# MEM.net
KiCad netlist of a schematic drawn in Altium Designer
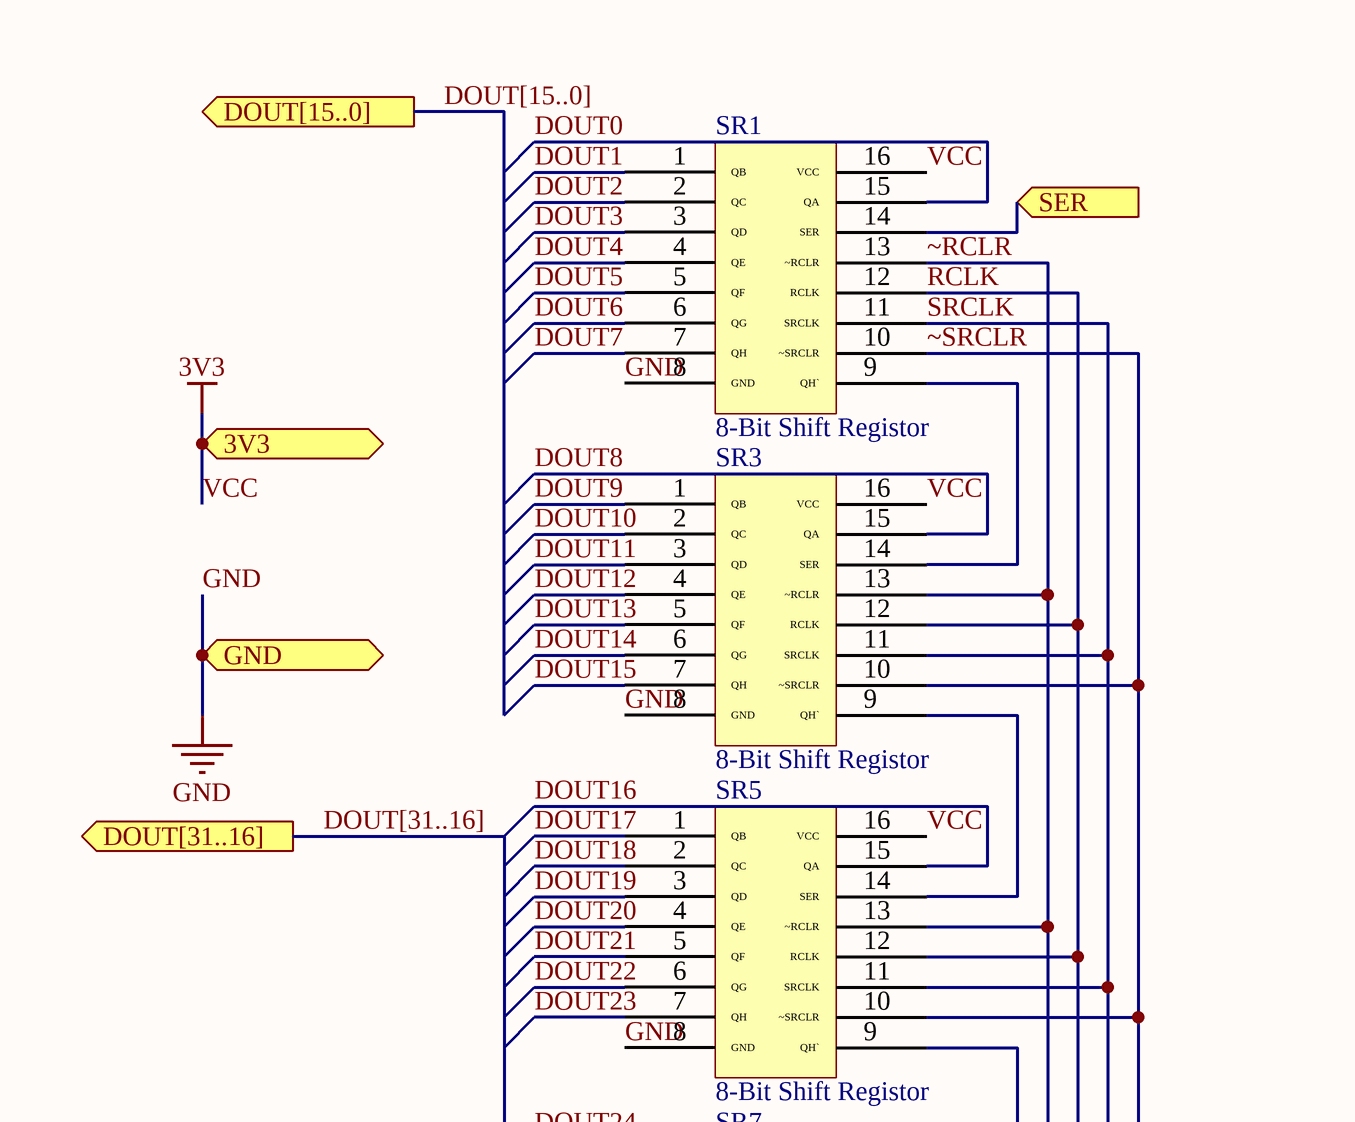
[diagram p0: MEM.SchDoc, top left]
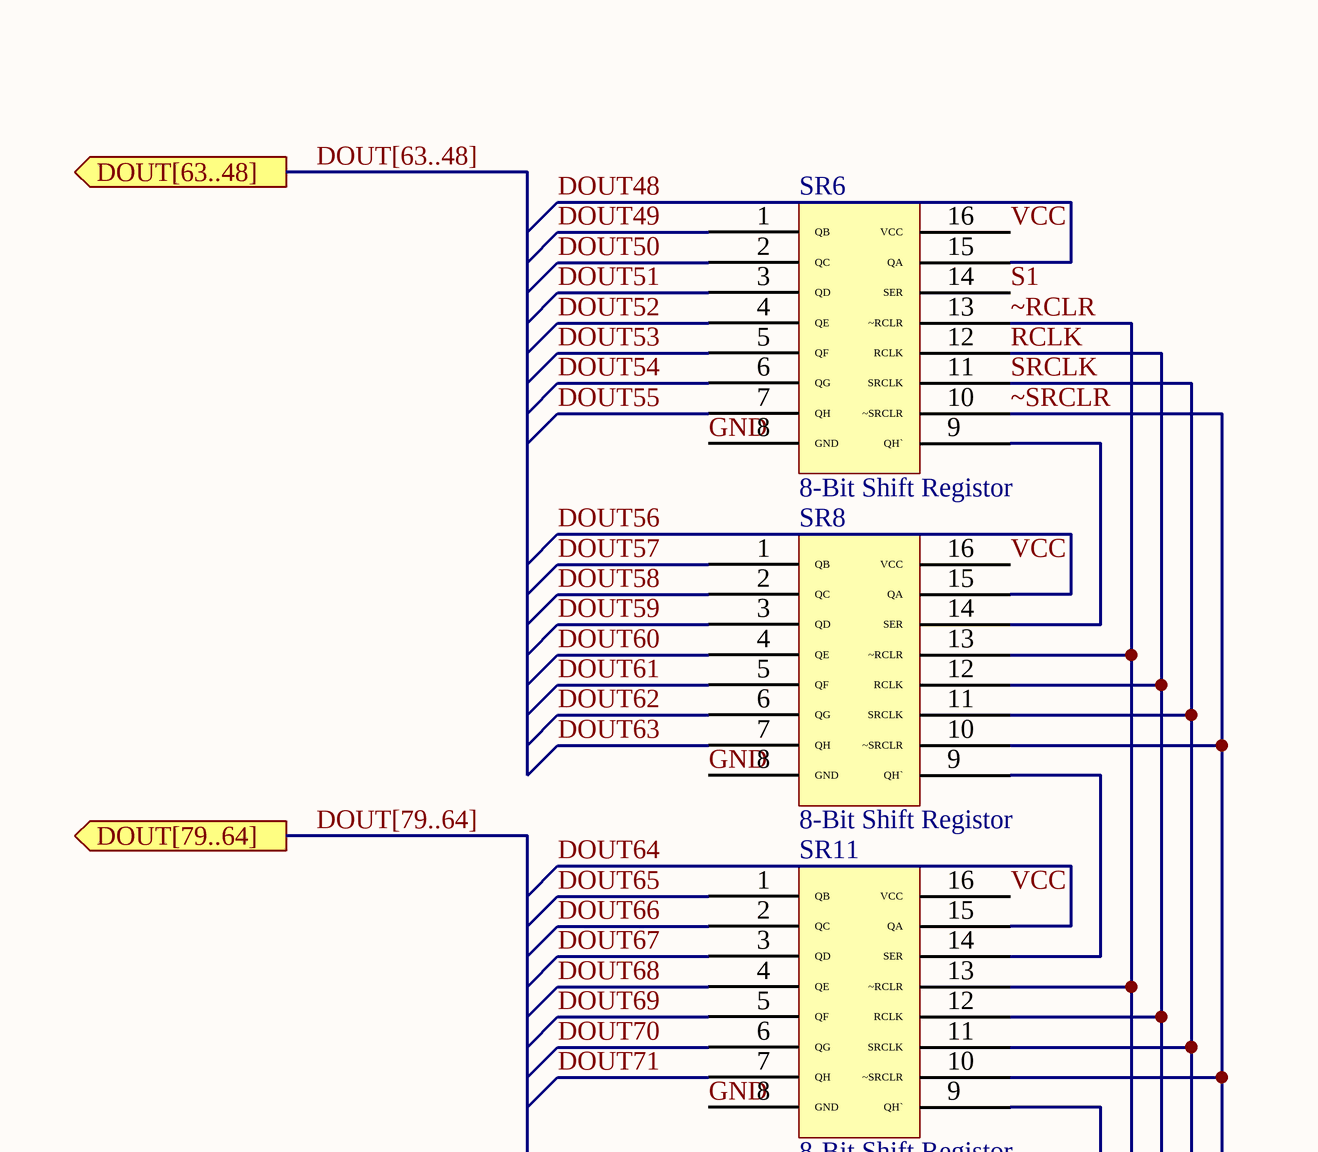
[diagram p1: MEM.SchDoc, top middle]
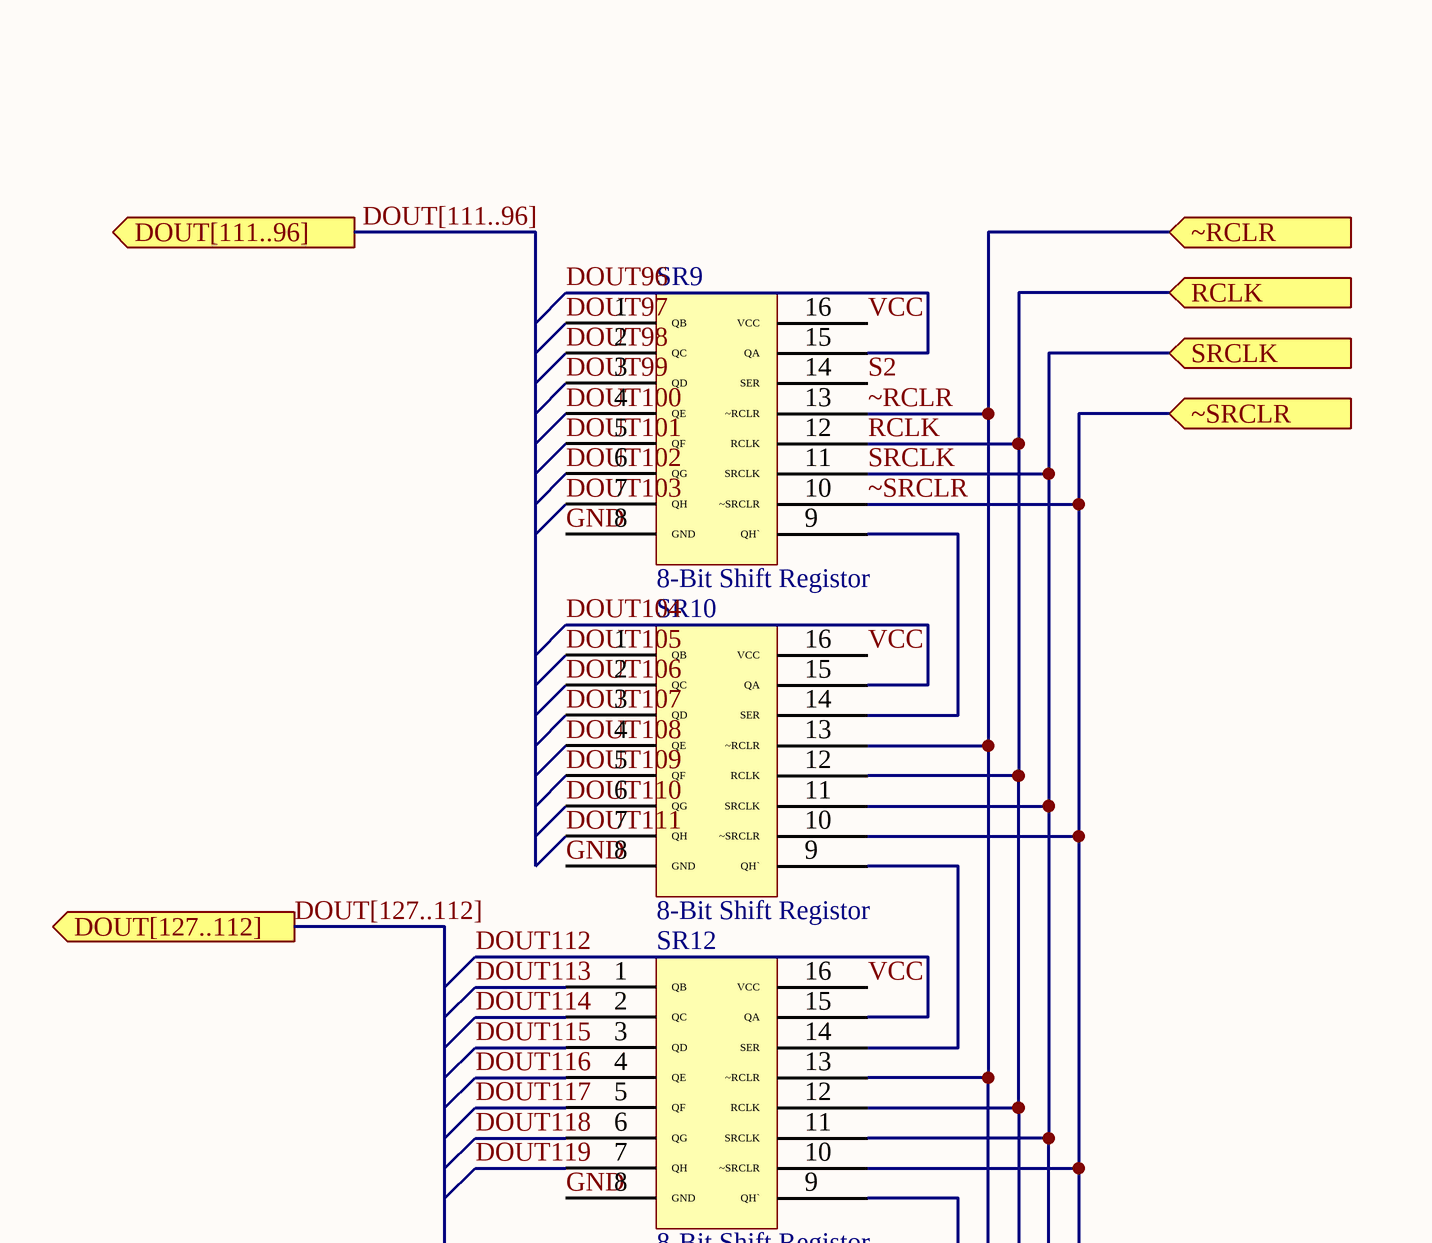
[diagram p2: MEM.SchDoc, top right]
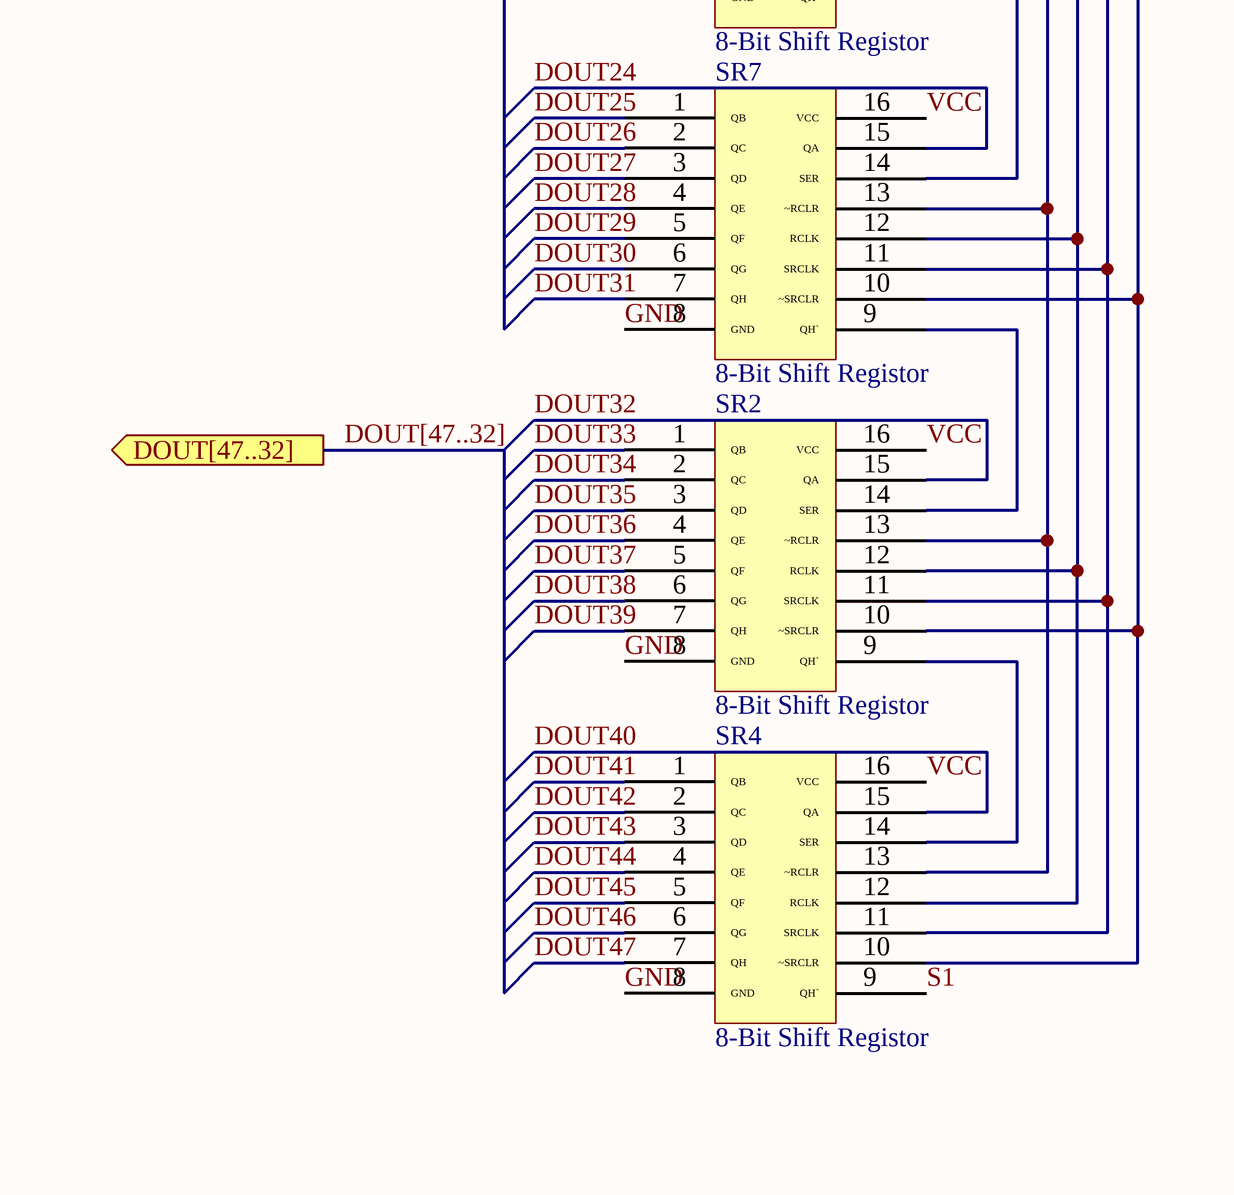
[diagram p3: MEM.SchDoc, bottom left]
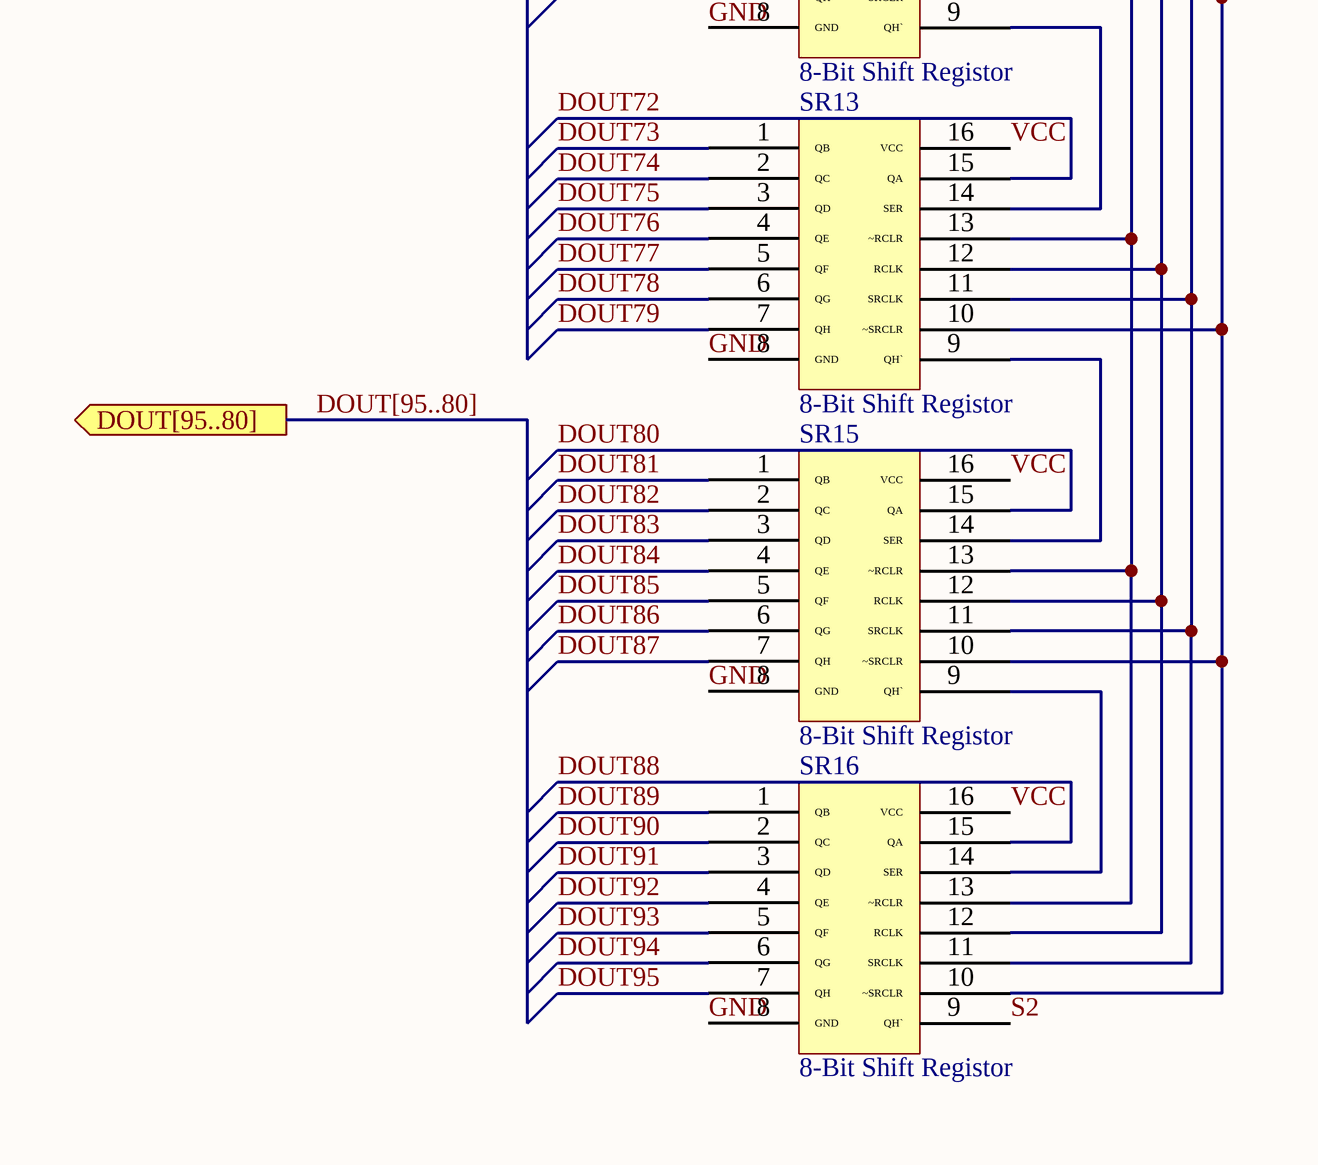
[diagram p4: MEM.SchDoc, bottom middle]
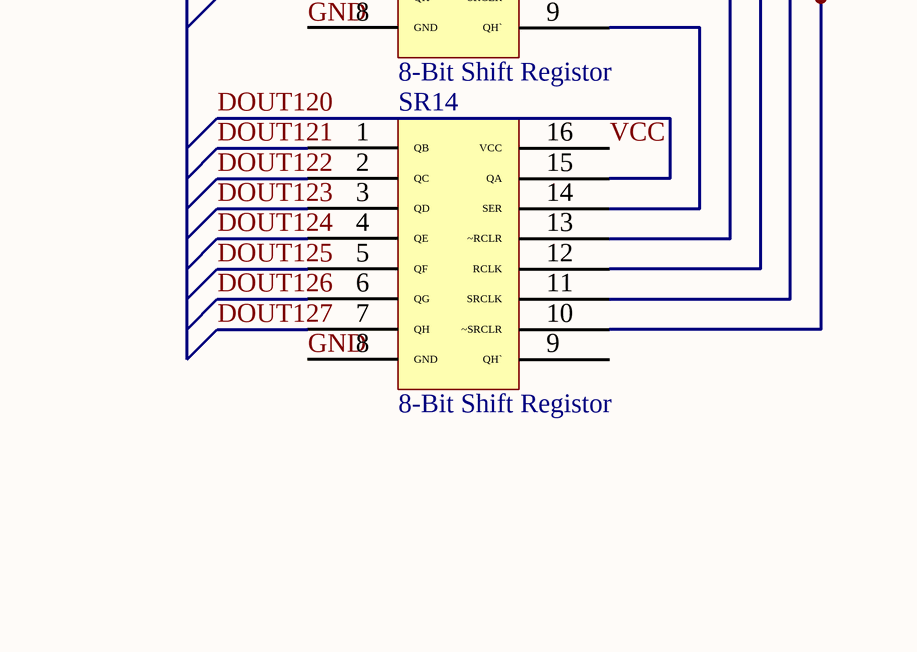
[diagram p5: MEM.SchDoc, bottom right]

(export (version "E")
  (design (tool "Eeschema 10.0.6"))
  (components
    (comp (ref "SR1")
      (value "8-Bit Shift Registor")
      (libsource (lib "NORMS_LIB") (part "8-Bit Shift Registor"))
    )
    (comp (ref "SR2")
      (value "8-Bit Shift Registor")
      (libsource (lib "NORMS_LIB") (part "8-Bit Shift Registor"))
    )
    (comp (ref "SR3")
      (value "8-Bit Shift Registor")
      (libsource (lib "NORMS_LIB") (part "8-Bit Shift Registor"))
    )
    (comp (ref "SR4")
      (value "8-Bit Shift Registor")
      (libsource (lib "NORMS_LIB") (part "8-Bit Shift Registor"))
    )
    (comp (ref "SR5")
      (value "8-Bit Shift Registor")
      (libsource (lib "NORMS_LIB") (part "8-Bit Shift Registor"))
    )
    (comp (ref "SR6")
      (value "8-Bit Shift Registor")
      (libsource (lib "NORMS_LIB") (part "8-Bit Shift Registor"))
    )
    (comp (ref "SR7")
      (value "8-Bit Shift Registor")
      (libsource (lib "NORMS_LIB") (part "8-Bit Shift Registor"))
    )
    (comp (ref "SR8")
      (value "8-Bit Shift Registor")
      (libsource (lib "NORMS_LIB") (part "8-Bit Shift Registor"))
    )
    (comp (ref "SR9")
      (value "8-Bit Shift Registor")
      (libsource (lib "NORMS_LIB") (part "8-Bit Shift Registor"))
    )
    (comp (ref "SR10")
      (value "8-Bit Shift Registor")
      (libsource (lib "NORMS_LIB") (part "8-Bit Shift Registor"))
    )
    (comp (ref "SR11")
      (value "8-Bit Shift Registor")
      (libsource (lib "NORMS_LIB") (part "8-Bit Shift Registor"))
    )
    (comp (ref "SR12")
      (value "8-Bit Shift Registor")
      (libsource (lib "NORMS_LIB") (part "8-Bit Shift Registor"))
    )
    (comp (ref "SR13")
      (value "8-Bit Shift Registor")
      (libsource (lib "NORMS_LIB") (part "8-Bit Shift Registor"))
    )
    (comp (ref "SR14")
      (value "8-Bit Shift Registor")
      (libsource (lib "NORMS_LIB") (part "8-Bit Shift Registor"))
    )
    (comp (ref "SR15")
      (value "8-Bit Shift Registor")
      (libsource (lib "NORMS_LIB") (part "8-Bit Shift Registor"))
    )
    (comp (ref "SR16")
      (value "8-Bit Shift Registor")
      (libsource (lib "NORMS_LIB") (part "8-Bit Shift Registor"))
    )
  )
  (nets
    (net (code "1") (name "/DOUT0") (class "Default")
      (node (ref "SR1") (pin "15") (pinfunction "QA_15") (pintype "passive"))
    )
    (net (code "2") (name "/DOUT1") (class "Default")
      (node (ref "SR1") (pin "1") (pinfunction "QB_1") (pintype "passive"))
    )
    (net (code "3") (name "/DOUT2") (class "Default")
      (node (ref "SR1") (pin "2") (pinfunction "QC_2") (pintype "passive"))
    )
    (net (code "4") (name "/DOUT3") (class "Default")
      (node (ref "SR1") (pin "3") (pinfunction "QD_3") (pintype "passive"))
    )
    (net (code "5") (name "/DOUT4") (class "Default")
      (node (ref "SR1") (pin "4") (pinfunction "QE_4") (pintype "passive"))
    )
    (net (code "6") (name "/DOUT5") (class "Default")
      (node (ref "SR1") (pin "5") (pinfunction "QF_5") (pintype "passive"))
    )
    (net (code "7") (name "/DOUT6") (class "Default")
      (node (ref "SR1") (pin "6") (pinfunction "QG_6") (pintype "passive"))
    )
    (net (code "8") (name "/DOUT7") (class "Default")
      (node (ref "SR1") (pin "7") (pinfunction "QH_7") (pintype "passive"))
    )
    (net (code "9") (name "/DOUT8") (class "Default")
      (node (ref "SR3") (pin "15") (pinfunction "QA_15") (pintype "passive"))
    )
    (net (code "10") (name "/DOUT9") (class "Default")
      (node (ref "SR3") (pin "1") (pinfunction "QB_1") (pintype "passive"))
    )
    (net (code "11") (name "/DOUT10") (class "Default")
      (node (ref "SR3") (pin "2") (pinfunction "QC_2") (pintype "passive"))
    )
    (net (code "12") (name "/DOUT11") (class "Default")
      (node (ref "SR3") (pin "3") (pinfunction "QD_3") (pintype "passive"))
    )
    (net (code "13") (name "/DOUT12") (class "Default")
      (node (ref "SR3") (pin "4") (pinfunction "QE_4") (pintype "passive"))
    )
    (net (code "14") (name "/DOUT13") (class "Default")
      (node (ref "SR3") (pin "5") (pinfunction "QF_5") (pintype "passive"))
    )
    (net (code "15") (name "/DOUT14") (class "Default")
      (node (ref "SR3") (pin "6") (pinfunction "QG_6") (pintype "passive"))
    )
    (net (code "16") (name "/DOUT15") (class "Default")
      (node (ref "SR3") (pin "7") (pinfunction "QH_7") (pintype "passive"))
    )
    (net (code "17") (name "/DOUT16") (class "Default")
      (node (ref "SR5") (pin "15") (pinfunction "QA_15") (pintype "passive"))
    )
    (net (code "18") (name "/DOUT17") (class "Default")
      (node (ref "SR5") (pin "1") (pinfunction "QB_1") (pintype "passive"))
    )
    (net (code "19") (name "/DOUT18") (class "Default")
      (node (ref "SR5") (pin "2") (pinfunction "QC_2") (pintype "passive"))
    )
    (net (code "20") (name "/DOUT19") (class "Default")
      (node (ref "SR5") (pin "3") (pinfunction "QD_3") (pintype "passive"))
    )
    (net (code "21") (name "/DOUT20") (class "Default")
      (node (ref "SR5") (pin "4") (pinfunction "QE_4") (pintype "passive"))
    )
    (net (code "22") (name "/DOUT21") (class "Default")
      (node (ref "SR5") (pin "5") (pinfunction "QF_5") (pintype "passive"))
    )
    (net (code "23") (name "/DOUT22") (class "Default")
      (node (ref "SR5") (pin "6") (pinfunction "QG_6") (pintype "passive"))
    )
    (net (code "24") (name "/DOUT23") (class "Default")
      (node (ref "SR5") (pin "7") (pinfunction "QH_7") (pintype "passive"))
    )
    (net (code "25") (name "/DOUT24") (class "Default")
      (node (ref "SR7") (pin "15") (pinfunction "QA_15") (pintype "passive"))
    )
    (net (code "26") (name "/DOUT25") (class "Default")
      (node (ref "SR7") (pin "1") (pinfunction "QB_1") (pintype "passive"))
    )
    (net (code "27") (name "/DOUT26") (class "Default")
      (node (ref "SR7") (pin "2") (pinfunction "QC_2") (pintype "passive"))
    )
    (net (code "28") (name "/DOUT27") (class "Default")
      (node (ref "SR7") (pin "3") (pinfunction "QD_3") (pintype "passive"))
    )
    (net (code "29") (name "/DOUT28") (class "Default")
      (node (ref "SR7") (pin "4") (pinfunction "QE_4") (pintype "passive"))
    )
    (net (code "30") (name "/DOUT29") (class "Default")
      (node (ref "SR7") (pin "5") (pinfunction "QF_5") (pintype "passive"))
    )
    (net (code "31") (name "/DOUT30") (class "Default")
      (node (ref "SR7") (pin "6") (pinfunction "QG_6") (pintype "passive"))
    )
    (net (code "32") (name "/DOUT31") (class "Default")
      (node (ref "SR7") (pin "7") (pinfunction "QH_7") (pintype "passive"))
    )
    (net (code "33") (name "/DOUT32") (class "Default")
      (node (ref "SR2") (pin "15") (pinfunction "QA_15") (pintype "passive"))
    )
    (net (code "34") (name "/DOUT33") (class "Default")
      (node (ref "SR2") (pin "1") (pinfunction "QB_1") (pintype "passive"))
    )
    (net (code "35") (name "/DOUT34") (class "Default")
      (node (ref "SR2") (pin "2") (pinfunction "QC_2") (pintype "passive"))
    )
    (net (code "36") (name "/DOUT35") (class "Default")
      (node (ref "SR2") (pin "3") (pinfunction "QD_3") (pintype "passive"))
    )
    (net (code "37") (name "/DOUT36") (class "Default")
      (node (ref "SR2") (pin "4") (pinfunction "QE_4") (pintype "passive"))
    )
    (net (code "38") (name "/DOUT37") (class "Default")
      (node (ref "SR2") (pin "5") (pinfunction "QF_5") (pintype "passive"))
    )
    (net (code "39") (name "/DOUT38") (class "Default")
      (node (ref "SR2") (pin "6") (pinfunction "QG_6") (pintype "passive"))
    )
    (net (code "40") (name "/DOUT39") (class "Default")
      (node (ref "SR2") (pin "7") (pinfunction "QH_7") (pintype "passive"))
    )
    (net (code "41") (name "/DOUT40") (class "Default")
      (node (ref "SR4") (pin "15") (pinfunction "QA_15") (pintype "passive"))
    )
    (net (code "42") (name "/DOUT41") (class "Default")
      (node (ref "SR4") (pin "1") (pinfunction "QB_1") (pintype "passive"))
    )
    (net (code "43") (name "/DOUT42") (class "Default")
      (node (ref "SR4") (pin "2") (pinfunction "QC_2") (pintype "passive"))
    )
    (net (code "44") (name "/DOUT43") (class "Default")
      (node (ref "SR4") (pin "3") (pinfunction "QD_3") (pintype "passive"))
    )
    (net (code "45") (name "/DOUT44") (class "Default")
      (node (ref "SR4") (pin "4") (pinfunction "QE_4") (pintype "passive"))
    )
    (net (code "46") (name "/DOUT45") (class "Default")
      (node (ref "SR4") (pin "5") (pinfunction "QF_5") (pintype "passive"))
    )
    (net (code "47") (name "/DOUT46") (class "Default")
      (node (ref "SR4") (pin "6") (pinfunction "QG_6") (pintype "passive"))
    )
    (net (code "48") (name "/DOUT47") (class "Default")
      (node (ref "SR4") (pin "7") (pinfunction "QH_7") (pintype "passive"))
    )
    (net (code "49") (name "/DOUT48") (class "Default")
      (node (ref "SR6") (pin "15") (pinfunction "QA_15") (pintype "passive"))
    )
    (net (code "50") (name "/DOUT49") (class "Default")
      (node (ref "SR6") (pin "1") (pinfunction "QB_1") (pintype "passive"))
    )
    (net (code "51") (name "/DOUT50") (class "Default")
      (node (ref "SR6") (pin "2") (pinfunction "QC_2") (pintype "passive"))
    )
    (net (code "52") (name "/DOUT51") (class "Default")
      (node (ref "SR6") (pin "3") (pinfunction "QD_3") (pintype "passive"))
    )
    (net (code "53") (name "/DOUT52") (class "Default")
      (node (ref "SR6") (pin "4") (pinfunction "QE_4") (pintype "passive"))
    )
    (net (code "54") (name "/DOUT53") (class "Default")
      (node (ref "SR6") (pin "5") (pinfunction "QF_5") (pintype "passive"))
    )
    (net (code "55") (name "/DOUT54") (class "Default")
      (node (ref "SR6") (pin "6") (pinfunction "QG_6") (pintype "passive"))
    )
    (net (code "56") (name "/DOUT55") (class "Default")
      (node (ref "SR6") (pin "7") (pinfunction "QH_7") (pintype "passive"))
    )
    (net (code "57") (name "/DOUT56") (class "Default")
      (node (ref "SR8") (pin "15") (pinfunction "QA_15") (pintype "passive"))
    )
    (net (code "58") (name "/DOUT57") (class "Default")
      (node (ref "SR8") (pin "1") (pinfunction "QB_1") (pintype "passive"))
    )
    (net (code "59") (name "/DOUT58") (class "Default")
      (node (ref "SR8") (pin "2") (pinfunction "QC_2") (pintype "passive"))
    )
    (net (code "60") (name "/DOUT59") (class "Default")
      (node (ref "SR8") (pin "3") (pinfunction "QD_3") (pintype "passive"))
    )
    (net (code "61") (name "/DOUT60") (class "Default")
      (node (ref "SR8") (pin "4") (pinfunction "QE_4") (pintype "passive"))
    )
    (net (code "62") (name "/DOUT61") (class "Default")
      (node (ref "SR8") (pin "5") (pinfunction "QF_5") (pintype "passive"))
    )
    (net (code "63") (name "/DOUT62") (class "Default")
      (node (ref "SR8") (pin "6") (pinfunction "QG_6") (pintype "passive"))
    )
    (net (code "64") (name "/DOUT63") (class "Default")
      (node (ref "SR8") (pin "7") (pinfunction "QH_7") (pintype "passive"))
    )
    (net (code "65") (name "/DOUT64") (class "Default")
      (node (ref "SR11") (pin "15") (pinfunction "QA_15") (pintype "passive"))
    )
    (net (code "66") (name "/DOUT65") (class "Default")
      (node (ref "SR11") (pin "1") (pinfunction "QB_1") (pintype "passive"))
    )
    (net (code "67") (name "/DOUT66") (class "Default")
      (node (ref "SR11") (pin "2") (pinfunction "QC_2") (pintype "passive"))
    )
    (net (code "68") (name "/DOUT67") (class "Default")
      (node (ref "SR11") (pin "3") (pinfunction "QD_3") (pintype "passive"))
    )
    (net (code "69") (name "/DOUT68") (class "Default")
      (node (ref "SR11") (pin "4") (pinfunction "QE_4") (pintype "passive"))
    )
    (net (code "70") (name "/DOUT69") (class "Default")
      (node (ref "SR11") (pin "5") (pinfunction "QF_5") (pintype "passive"))
    )
    (net (code "71") (name "/DOUT70") (class "Default")
      (node (ref "SR11") (pin "6") (pinfunction "QG_6") (pintype "passive"))
    )
    (net (code "72") (name "/DOUT71") (class "Default")
      (node (ref "SR11") (pin "7") (pinfunction "QH_7") (pintype "passive"))
    )
    (net (code "73") (name "/DOUT72") (class "Default")
      (node (ref "SR13") (pin "15") (pinfunction "QA_15") (pintype "passive"))
    )
    (net (code "74") (name "/DOUT73") (class "Default")
      (node (ref "SR13") (pin "1") (pinfunction "QB_1") (pintype "passive"))
    )
    (net (code "75") (name "/DOUT74") (class "Default")
      (node (ref "SR13") (pin "2") (pinfunction "QC_2") (pintype "passive"))
    )
    (net (code "76") (name "/DOUT75") (class "Default")
      (node (ref "SR13") (pin "3") (pinfunction "QD_3") (pintype "passive"))
    )
    (net (code "77") (name "/DOUT76") (class "Default")
      (node (ref "SR13") (pin "4") (pinfunction "QE_4") (pintype "passive"))
    )
    (net (code "78") (name "/DOUT77") (class "Default")
      (node (ref "SR13") (pin "5") (pinfunction "QF_5") (pintype "passive"))
    )
    (net (code "79") (name "/DOUT78") (class "Default")
      (node (ref "SR13") (pin "6") (pinfunction "QG_6") (pintype "passive"))
    )
    (net (code "80") (name "/DOUT79") (class "Default")
      (node (ref "SR13") (pin "7") (pinfunction "QH_7") (pintype "passive"))
    )
    (net (code "81") (name "/DOUT80") (class "Default")
      (node (ref "SR15") (pin "15") (pinfunction "QA_15") (pintype "passive"))
    )
    (net (code "82") (name "/DOUT81") (class "Default")
      (node (ref "SR15") (pin "1") (pinfunction "QB_1") (pintype "passive"))
    )
    (net (code "83") (name "/DOUT82") (class "Default")
      (node (ref "SR15") (pin "2") (pinfunction "QC_2") (pintype "passive"))
    )
    (net (code "84") (name "/DOUT83") (class "Default")
      (node (ref "SR15") (pin "3") (pinfunction "QD_3") (pintype "passive"))
    )
    (net (code "85") (name "/DOUT84") (class "Default")
      (node (ref "SR15") (pin "4") (pinfunction "QE_4") (pintype "passive"))
    )
    (net (code "86") (name "/DOUT85") (class "Default")
      (node (ref "SR15") (pin "5") (pinfunction "QF_5") (pintype "passive"))
    )
    (net (code "87") (name "/DOUT86") (class "Default")
      (node (ref "SR15") (pin "6") (pinfunction "QG_6") (pintype "passive"))
    )
    (net (code "88") (name "/DOUT87") (class "Default")
      (node (ref "SR15") (pin "7") (pinfunction "QH_7") (pintype "passive"))
    )
    (net (code "89") (name "/DOUT88") (class "Default")
      (node (ref "SR16") (pin "15") (pinfunction "QA_15") (pintype "passive"))
    )
    (net (code "90") (name "/DOUT89") (class "Default")
      (node (ref "SR16") (pin "1") (pinfunction "QB_1") (pintype "passive"))
    )
    (net (code "91") (name "/DOUT90") (class "Default")
      (node (ref "SR16") (pin "2") (pinfunction "QC_2") (pintype "passive"))
    )
    (net (code "92") (name "/DOUT91") (class "Default")
      (node (ref "SR16") (pin "3") (pinfunction "QD_3") (pintype "passive"))
    )
    (net (code "93") (name "/DOUT92") (class "Default")
      (node (ref "SR16") (pin "4") (pinfunction "QE_4") (pintype "passive"))
    )
    (net (code "94") (name "/DOUT93") (class "Default")
      (node (ref "SR16") (pin "5") (pinfunction "QF_5") (pintype "passive"))
    )
    (net (code "95") (name "/DOUT94") (class "Default")
      (node (ref "SR16") (pin "6") (pinfunction "QG_6") (pintype "passive"))
    )
    (net (code "96") (name "/DOUT95") (class "Default")
      (node (ref "SR16") (pin "7") (pinfunction "QH_7") (pintype "passive"))
    )
    (net (code "97") (name "/DOUT96") (class "Default")
      (node (ref "SR9") (pin "15") (pinfunction "QA_15") (pintype "passive"))
    )
    (net (code "98") (name "/DOUT97") (class "Default")
      (node (ref "SR9") (pin "1") (pinfunction "QB_1") (pintype "passive"))
    )
    (net (code "99") (name "/DOUT98") (class "Default")
      (node (ref "SR9") (pin "2") (pinfunction "QC_2") (pintype "passive"))
    )
    (net (code "100") (name "/DOUT99") (class "Default")
      (node (ref "SR9") (pin "3") (pinfunction "QD_3") (pintype "passive"))
    )
    (net (code "101") (name "/DOUT100") (class "Default")
      (node (ref "SR9") (pin "4") (pinfunction "QE_4") (pintype "passive"))
    )
    (net (code "102") (name "/DOUT101") (class "Default")
      (node (ref "SR9") (pin "5") (pinfunction "QF_5") (pintype "passive"))
    )
    (net (code "103") (name "/DOUT102") (class "Default")
      (node (ref "SR9") (pin "6") (pinfunction "QG_6") (pintype "passive"))
    )
    (net (code "104") (name "/DOUT103") (class "Default")
      (node (ref "SR9") (pin "7") (pinfunction "QH_7") (pintype "passive"))
    )
    (net (code "105") (name "/DOUT104") (class "Default")
      (node (ref "SR10") (pin "15") (pinfunction "QA_15") (pintype "passive"))
    )
    (net (code "106") (name "/DOUT105") (class "Default")
      (node (ref "SR10") (pin "1") (pinfunction "QB_1") (pintype "passive"))
    )
    (net (code "107") (name "/DOUT106") (class "Default")
      (node (ref "SR10") (pin "2") (pinfunction "QC_2") (pintype "passive"))
    )
    (net (code "108") (name "/DOUT107") (class "Default")
      (node (ref "SR10") (pin "3") (pinfunction "QD_3") (pintype "passive"))
    )
    (net (code "109") (name "/DOUT108") (class "Default")
      (node (ref "SR10") (pin "4") (pinfunction "QE_4") (pintype "passive"))
    )
    (net (code "110") (name "/DOUT109") (class "Default")
      (node (ref "SR10") (pin "5") (pinfunction "QF_5") (pintype "passive"))
    )
    (net (code "111") (name "/DOUT110") (class "Default")
      (node (ref "SR10") (pin "6") (pinfunction "QG_6") (pintype "passive"))
    )
    (net (code "112") (name "/DOUT111") (class "Default")
      (node (ref "SR10") (pin "7") (pinfunction "QH_7") (pintype "passive"))
    )
    (net (code "113") (name "/DOUT112") (class "Default")
      (node (ref "SR12") (pin "15") (pinfunction "QA_15") (pintype "passive"))
    )
    (net (code "114") (name "/DOUT113") (class "Default")
      (node (ref "SR12") (pin "1") (pinfunction "QB_1") (pintype "passive"))
    )
    (net (code "115") (name "/DOUT114") (class "Default")
      (node (ref "SR12") (pin "2") (pinfunction "QC_2") (pintype "passive"))
    )
    (net (code "116") (name "/DOUT115") (class "Default")
      (node (ref "SR12") (pin "3") (pinfunction "QD_3") (pintype "passive"))
    )
    (net (code "117") (name "/DOUT116") (class "Default")
      (node (ref "SR12") (pin "4") (pinfunction "QE_4") (pintype "passive"))
    )
    (net (code "118") (name "/DOUT117") (class "Default")
      (node (ref "SR12") (pin "5") (pinfunction "QF_5") (pintype "passive"))
    )
    (net (code "119") (name "/DOUT118") (class "Default")
      (node (ref "SR12") (pin "6") (pinfunction "QG_6") (pintype "passive"))
    )
    (net (code "120") (name "/DOUT119") (class "Default")
      (node (ref "SR12") (pin "7") (pinfunction "QH_7") (pintype "passive"))
    )
    (net (code "121") (name "/DOUT120") (class "Default")
      (node (ref "SR14") (pin "15") (pinfunction "QA_15") (pintype "passive"))
    )
    (net (code "122") (name "/DOUT121") (class "Default")
      (node (ref "SR14") (pin "1") (pinfunction "QB_1") (pintype "passive"))
    )
    (net (code "123") (name "/DOUT122") (class "Default")
      (node (ref "SR14") (pin "2") (pinfunction "QC_2") (pintype "passive"))
    )
    (net (code "124") (name "/DOUT123") (class "Default")
      (node (ref "SR14") (pin "3") (pinfunction "QD_3") (pintype "passive"))
    )
    (net (code "125") (name "/DOUT124") (class "Default")
      (node (ref "SR14") (pin "4") (pinfunction "QE_4") (pintype "passive"))
    )
    (net (code "126") (name "/DOUT125") (class "Default")
      (node (ref "SR14") (pin "5") (pinfunction "QF_5") (pintype "passive"))
    )
    (net (code "127") (name "/DOUT126") (class "Default")
      (node (ref "SR14") (pin "6") (pinfunction "QG_6") (pintype "passive"))
    )
    (net (code "128") (name "/DOUT127") (class "Default")
      (node (ref "SR14") (pin "7") (pinfunction "QH_7") (pintype "passive"))
    )
    (net (code "137") (name "/RCLK") (class "Default")
      (node (ref "SR1") (pin "12") (pinfunction "RCLK_12") (pintype "passive"))
      (node (ref "SR10") (pin "12") (pinfunction "RCLK_12") (pintype "passive"))
      (node (ref "SR11") (pin "12") (pinfunction "RCLK_12") (pintype "passive"))
      (node (ref "SR12") (pin "12") (pinfunction "RCLK_12") (pintype "passive"))
      (node (ref "SR13") (pin "12") (pinfunction "RCLK_12") (pintype "passive"))
      (node (ref "SR14") (pin "12") (pinfunction "RCLK_12") (pintype "passive"))
      (node (ref "SR15") (pin "12") (pinfunction "RCLK_12") (pintype "passive"))
      (node (ref "SR16") (pin "12") (pinfunction "RCLK_12") (pintype "passive"))
      (node (ref "SR2") (pin "12") (pinfunction "RCLK_12") (pintype "passive"))
      (node (ref "SR3") (pin "12") (pinfunction "RCLK_12") (pintype "passive"))
      (node (ref "SR4") (pin "12") (pinfunction "RCLK_12") (pintype "passive"))
      (node (ref "SR5") (pin "12") (pinfunction "RCLK_12") (pintype "passive"))
      (node (ref "SR6") (pin "12") (pinfunction "RCLK_12") (pintype "passive"))
      (node (ref "SR7") (pin "12") (pinfunction "RCLK_12") (pintype "passive"))
      (node (ref "SR8") (pin "12") (pinfunction "RCLK_12") (pintype "passive"))
      (node (ref "SR9") (pin "12") (pinfunction "RCLK_12") (pintype "passive"))
    )
    (net (code "138") (name "/S1") (class "Default")
      (node (ref "SR4") (pin "9") (pinfunction "QH`_9") (pintype "passive"))
      (node (ref "SR6") (pin "14") (pinfunction "SER_14") (pintype "passive"))
    )
    (net (code "139") (name "/S2") (class "Default")
      (node (ref "SR16") (pin "9") (pinfunction "QH`_9") (pintype "passive"))
      (node (ref "SR9") (pin "14") (pinfunction "SER_14") (pintype "passive"))
    )
    (net (code "140") (name "/SER") (class "Default")
      (node (ref "SR1") (pin "14") (pinfunction "SER_14") (pintype "passive"))
    )
    (net (code "141") (name "/SRCLK") (class "Default")
      (node (ref "SR1") (pin "11") (pinfunction "SRCLK_11") (pintype "passive"))
      (node (ref "SR10") (pin "11") (pinfunction "SRCLK_11") (pintype "passive"))
      (node (ref "SR11") (pin "11") (pinfunction "SRCLK_11") (pintype "passive"))
      (node (ref "SR12") (pin "11") (pinfunction "SRCLK_11") (pintype "passive"))
      (node (ref "SR13") (pin "11") (pinfunction "SRCLK_11") (pintype "passive"))
      (node (ref "SR14") (pin "11") (pinfunction "SRCLK_11") (pintype "passive"))
      (node (ref "SR15") (pin "11") (pinfunction "SRCLK_11") (pintype "passive"))
      (node (ref "SR16") (pin "11") (pinfunction "SRCLK_11") (pintype "passive"))
      (node (ref "SR2") (pin "11") (pinfunction "SRCLK_11") (pintype "passive"))
      (node (ref "SR3") (pin "11") (pinfunction "SRCLK_11") (pintype "passive"))
      (node (ref "SR4") (pin "11") (pinfunction "SRCLK_11") (pintype "passive"))
      (node (ref "SR5") (pin "11") (pinfunction "SRCLK_11") (pintype "passive"))
      (node (ref "SR6") (pin "11") (pinfunction "SRCLK_11") (pintype "passive"))
      (node (ref "SR7") (pin "11") (pinfunction "SRCLK_11") (pintype "passive"))
      (node (ref "SR8") (pin "11") (pinfunction "SRCLK_11") (pintype "passive"))
      (node (ref "SR9") (pin "11") (pinfunction "SRCLK_11") (pintype "passive"))
    )
    (net (code "142") (name "/~RCLR") (class "Default")
      (node (ref "SR1") (pin "13") (pinfunction "~RCLR_13") (pintype "passive"))
      (node (ref "SR10") (pin "13") (pinfunction "~RCLR_13") (pintype "passive"))
      (node (ref "SR11") (pin "13") (pinfunction "~RCLR_13") (pintype "passive"))
      (node (ref "SR12") (pin "13") (pinfunction "~RCLR_13") (pintype "passive"))
      (node (ref "SR13") (pin "13") (pinfunction "~RCLR_13") (pintype "passive"))
      (node (ref "SR14") (pin "13") (pinfunction "~RCLR_13") (pintype "passive"))
      (node (ref "SR15") (pin "13") (pinfunction "~RCLR_13") (pintype "passive"))
      (node (ref "SR16") (pin "13") (pinfunction "~RCLR_13") (pintype "passive"))
      (node (ref "SR2") (pin "13") (pinfunction "~RCLR_13") (pintype "passive"))
      (node (ref "SR3") (pin "13") (pinfunction "~RCLR_13") (pintype "passive"))
      (node (ref "SR4") (pin "13") (pinfunction "~RCLR_13") (pintype "passive"))
      (node (ref "SR5") (pin "13") (pinfunction "~RCLR_13") (pintype "passive"))
      (node (ref "SR6") (pin "13") (pinfunction "~RCLR_13") (pintype "passive"))
      (node (ref "SR7") (pin "13") (pinfunction "~RCLR_13") (pintype "passive"))
      (node (ref "SR8") (pin "13") (pinfunction "~RCLR_13") (pintype "passive"))
      (node (ref "SR9") (pin "13") (pinfunction "~RCLR_13") (pintype "passive"))
    )
    (net (code "143") (name "/~SRCLR") (class "Default")
      (node (ref "SR1") (pin "10") (pinfunction "~SRCLR_10") (pintype "passive"))
      (node (ref "SR10") (pin "10") (pinfunction "~SRCLR_10") (pintype "passive"))
      (node (ref "SR11") (pin "10") (pinfunction "~SRCLR_10") (pintype "passive"))
      (node (ref "SR12") (pin "10") (pinfunction "~SRCLR_10") (pintype "passive"))
      (node (ref "SR13") (pin "10") (pinfunction "~SRCLR_10") (pintype "passive"))
      (node (ref "SR14") (pin "10") (pinfunction "~SRCLR_10") (pintype "passive"))
      (node (ref "SR15") (pin "10") (pinfunction "~SRCLR_10") (pintype "passive"))
      (node (ref "SR16") (pin "10") (pinfunction "~SRCLR_10") (pintype "passive"))
      (node (ref "SR2") (pin "10") (pinfunction "~SRCLR_10") (pintype "passive"))
      (node (ref "SR3") (pin "10") (pinfunction "~SRCLR_10") (pintype "passive"))
      (node (ref "SR4") (pin "10") (pinfunction "~SRCLR_10") (pintype "passive"))
      (node (ref "SR5") (pin "10") (pinfunction "~SRCLR_10") (pintype "passive"))
      (node (ref "SR6") (pin "10") (pinfunction "~SRCLR_10") (pintype "passive"))
      (node (ref "SR7") (pin "10") (pinfunction "~SRCLR_10") (pintype "passive"))
      (node (ref "SR8") (pin "10") (pinfunction "~SRCLR_10") (pintype "passive"))
      (node (ref "SR9") (pin "10") (pinfunction "~SRCLR_10") (pintype "passive"))
    )
    (net (code "144") (name "3V3") (class "Default")
      (node (ref "SR1") (pin "16") (pinfunction "VCC_16") (pintype "passive"))
      (node (ref "SR10") (pin "16") (pinfunction "VCC_16") (pintype "passive"))
      (node (ref "SR11") (pin "16") (pinfunction "VCC_16") (pintype "passive"))
      (node (ref "SR12") (pin "16") (pinfunction "VCC_16") (pintype "passive"))
      (node (ref "SR13") (pin "16") (pinfunction "VCC_16") (pintype "passive"))
      (node (ref "SR14") (pin "16") (pinfunction "VCC_16") (pintype "passive"))
      (node (ref "SR15") (pin "16") (pinfunction "VCC_16") (pintype "passive"))
      (node (ref "SR16") (pin "16") (pinfunction "VCC_16") (pintype "passive"))
      (node (ref "SR2") (pin "16") (pinfunction "VCC_16") (pintype "passive"))
      (node (ref "SR3") (pin "16") (pinfunction "VCC_16") (pintype "passive"))
      (node (ref "SR4") (pin "16") (pinfunction "VCC_16") (pintype "passive"))
      (node (ref "SR5") (pin "16") (pinfunction "VCC_16") (pintype "passive"))
      (node (ref "SR6") (pin "16") (pinfunction "VCC_16") (pintype "passive"))
      (node (ref "SR7") (pin "16") (pinfunction "VCC_16") (pintype "passive"))
      (node (ref "SR8") (pin "16") (pinfunction "VCC_16") (pintype "passive"))
      (node (ref "SR9") (pin "16") (pinfunction "VCC_16") (pintype "passive"))
    )
    (net (code "145") (name "GND") (class "Default")
      (node (ref "SR1") (pin "8") (pinfunction "GND_8") (pintype "passive"))
      (node (ref "SR10") (pin "8") (pinfunction "GND_8") (pintype "passive"))
      (node (ref "SR11") (pin "8") (pinfunction "GND_8") (pintype "passive"))
      (node (ref "SR12") (pin "8") (pinfunction "GND_8") (pintype "passive"))
      (node (ref "SR13") (pin "8") (pinfunction "GND_8") (pintype "passive"))
      (node (ref "SR14") (pin "8") (pinfunction "GND_8") (pintype "passive"))
      (node (ref "SR15") (pin "8") (pinfunction "GND_8") (pintype "passive"))
      (node (ref "SR16") (pin "8") (pinfunction "GND_8") (pintype "passive"))
      (node (ref "SR2") (pin "8") (pinfunction "GND_8") (pintype "passive"))
      (node (ref "SR3") (pin "8") (pinfunction "GND_8") (pintype "passive"))
      (node (ref "SR4") (pin "8") (pinfunction "GND_8") (pintype "passive"))
      (node (ref "SR5") (pin "8") (pinfunction "GND_8") (pintype "passive"))
      (node (ref "SR6") (pin "8") (pinfunction "GND_8") (pintype "passive"))
      (node (ref "SR7") (pin "8") (pinfunction "GND_8") (pintype "passive"))
      (node (ref "SR8") (pin "8") (pinfunction "GND_8") (pintype "passive"))
      (node (ref "SR9") (pin "8") (pinfunction "GND_8") (pintype "passive"))
    )
    (net (code "146") (name "Net-(SR1-QH`)") (class "Default")
      (node (ref "SR1") (pin "9") (pinfunction "QH`_9") (pintype "passive"))
      (node (ref "SR3") (pin "14") (pinfunction "SER_14") (pintype "passive"))
    )
    (net (code "147") (name "Net-(SR2-QH`)") (class "Default")
      (node (ref "SR2") (pin "9") (pinfunction "QH`_9") (pintype "passive"))
      (node (ref "SR4") (pin "14") (pinfunction "SER_14") (pintype "passive"))
    )
    (net (code "148") (name "Net-(SR2-SER)") (class "Default")
      (node (ref "SR2") (pin "14") (pinfunction "SER_14") (pintype "passive"))
      (node (ref "SR7") (pin "9") (pinfunction "QH`_9") (pintype "passive"))
    )
    (net (code "149") (name "Net-(SR3-QH`)") (class "Default")
      (node (ref "SR3") (pin "9") (pinfunction "QH`_9") (pintype "passive"))
      (node (ref "SR5") (pin "14") (pinfunction "SER_14") (pintype "passive"))
    )
    (net (code "150") (name "Net-(SR5-QH`)") (class "Default")
      (node (ref "SR5") (pin "9") (pinfunction "QH`_9") (pintype "passive"))
      (node (ref "SR7") (pin "14") (pinfunction "SER_14") (pintype "passive"))
    )
    (net (code "151") (name "Net-(SR6-QH`)") (class "Default")
      (node (ref "SR6") (pin "9") (pinfunction "QH`_9") (pintype "passive"))
      (node (ref "SR8") (pin "14") (pinfunction "SER_14") (pintype "passive"))
    )
    (net (code "152") (name "Net-(SR10-QH`)") (class "Default")
      (node (ref "SR10") (pin "9") (pinfunction "QH`_9") (pintype "passive"))
      (node (ref "SR12") (pin "14") (pinfunction "SER_14") (pintype "passive"))
    )
    (net (code "153") (name "Net-(SR10-SER)") (class "Default")
      (node (ref "SR10") (pin "14") (pinfunction "SER_14") (pintype "passive"))
      (node (ref "SR9") (pin "9") (pinfunction "QH`_9") (pintype "passive"))
    )
    (net (code "154") (name "Net-(SR11-QH`)") (class "Default")
      (node (ref "SR11") (pin "9") (pinfunction "QH`_9") (pintype "passive"))
      (node (ref "SR13") (pin "14") (pinfunction "SER_14") (pintype "passive"))
    )
    (net (code "155") (name "Net-(SR11-SER)") (class "Default")
      (node (ref "SR11") (pin "14") (pinfunction "SER_14") (pintype "passive"))
      (node (ref "SR8") (pin "9") (pinfunction "QH`_9") (pintype "passive"))
    )
    (net (code "156") (name "Net-(SR12-QH`)") (class "Default")
      (node (ref "SR12") (pin "9") (pinfunction "QH`_9") (pintype "passive"))
      (node (ref "SR14") (pin "14") (pinfunction "SER_14") (pintype "passive"))
    )
    (net (code "157") (name "Net-(SR13-QH`)") (class "Default")
      (node (ref "SR13") (pin "9") (pinfunction "QH`_9") (pintype "passive"))
      (node (ref "SR15") (pin "14") (pinfunction "SER_14") (pintype "passive"))
    )
    (net (code "158") (name "Net-(SR15-QH`)") (class "Default")
      (node (ref "SR15") (pin "9") (pinfunction "QH`_9") (pintype "passive"))
      (node (ref "SR16") (pin "14") (pinfunction "SER_14") (pintype "passive"))
    )
    (net (code "159") (name "unconnected-(SR14-QH`-Pad9)") (class "Default")
      (node (ref "SR14") (pin "9") (pinfunction "QH`_9") (pintype "passive"))
    )
  )
)
